# USBCONN_USBC16.net
KiCad netlist of a schematic drawn in Altium Designer
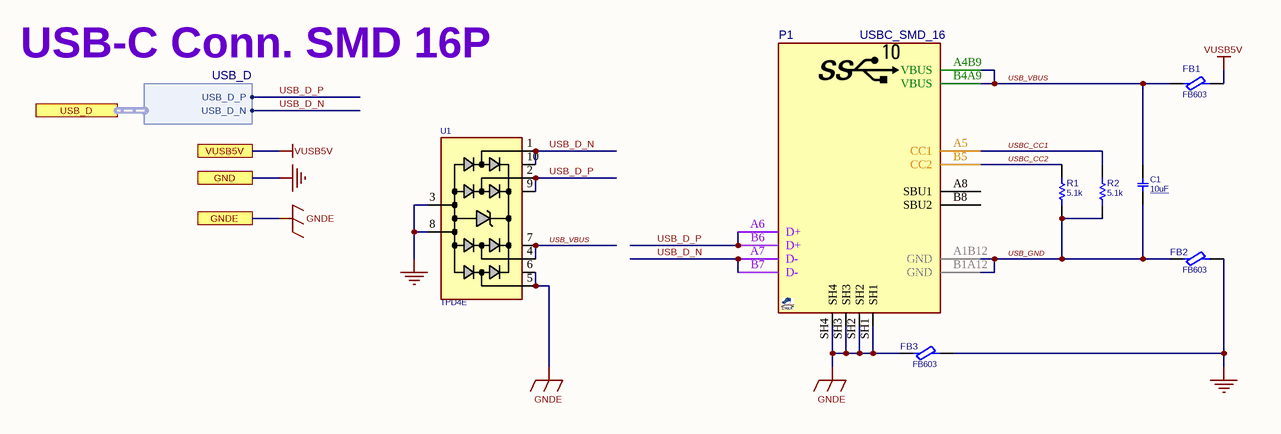
[diagram p0: USBCONN_USBC16.SchDoc]

(export (version "E")
  (design (tool "Eeschema 10.0.6"))
  (components
    (comp (ref "C1")
      (value "10uF")
      (footprint "C0402")
      (description "CAP, MLCC")
      (fields (field (name "MANF") "Murata"))
      (libsource (lib "mlcc_smd_passive") (part "CAP_SMD_MLCC"))
    )
    (comp (ref "FB1")
      (value "FB603")
      (footprint "L0603")
      (description "FERRITE_Bead, 0603, 1.3A, 150mOhm, 600@100MHz")
      (fields (field (name "MANF") "MURATA") (field (name "MANF_P#") "BLM18KG601SN1D"))
      (libsource (lib "emi_filter") (part "FBEAD_SMD_BLM18KG601"))
    )
    (comp (ref "FB2")
      (value "FB603")
      (footprint "L0603")
      (description "FERRITE_Bead, 0603, 1.3A, 150mOhm, 600@100MHz")
      (fields (field (name "MANF") "MURATA") (field (name "MANF_P#") "BLM18KG601SN1D"))
      (libsource (lib "emi_filter") (part "FBEAD_SMD_BLM18KG601"))
    )
    (comp (ref "FB3")
      (value "FB603")
      (footprint "L0603")
      (description "FERRITE_Bead, 0603, 1.3A, 150mOhm, 600@100MHz")
      (fields (field (name "MANF") "MURATA") (field (name "MANF_P#") "BLM18KG601SN1D"))
      (libsource (lib "emi_filter") (part "FBEAD_SMD_BLM18KG601"))
    )
    (comp (ref "P1")
      (value "USBC_SMD_16")
      (footprint "USBC_SMD_16_2171790001")
      (description "CONN, USB, Type C, USB 2.0, Right-Angle, SMD")
      (fields (field (name "MANF") "MOLEX") (field (name "MANF_P#") "2171790001"))
      (libsource (lib "USBC") (part "CONN_USBC_SMD_16_2171790001"))
    )
    (comp (ref "R1")
      (value "5.1k")
      (footprint "R0402")
      (description "RESISTOR, SMD")
      (libsource (lib "res_smd_passive") (part "RES_SMD"))
    )
    (comp (ref "R2")
      (value "5.1k")
      (footprint "R0402")
      (description "RESISTOR, SMD")
      (libsource (lib "res_smd_passive") (part "RES_SMD"))
    )
    (comp (ref "U1")
      (value "TPD4E")
      (footprint "SON50_10_2510E")
      (description "TVS, ESD PROTECT, 4CH,")
      (fields (field (name "MANF_P#") "TPD4E05U06DQA") (field (name "MANF") "Texas Instruments"))
      (libsource (lib "protect_tvs_esd_fuse") (part "TVS_X4_TPD4E05U06"))
    )
  )
  (nets
    (net (code "2") (name "/USBC_CC1") (class "Default")
      (node (ref "P1") (pin "A5") (pinfunction "CC1_A5") (pintype "passive"))
      (node (ref "R2") (pin "2") (pinfunction "2_2") (pintype "passive"))
    )
    (net (code "3") (name "/USBC_CC2") (class "Default")
      (node (ref "P1") (pin "B5") (pinfunction "CC2_B5") (pintype "passive"))
      (node (ref "R1") (pin "2") (pinfunction "2_2") (pintype "passive"))
    )
    (net (code "4") (name "/USB_D_N") (class "Default")
      (node (ref "P1") (pin "A7") (pinfunction "D-_A7") (pintype "passive"))
      (node (ref "P1") (pin "B7") (pinfunction "D-_B7") (pintype "passive"))
      (node (ref "U1") (pin "1") (pinfunction "1_1") (pintype "passive"))
      (node (ref "U1") (pin "10") (pinfunction "10_10") (pintype "passive"))
    )
    (net (code "5") (name "/USB_D_P") (class "Default")
      (node (ref "P1") (pin "A6") (pinfunction "D+_A6") (pintype "passive"))
      (node (ref "P1") (pin "B6") (pinfunction "D+_B6") (pintype "passive"))
      (node (ref "U1") (pin "2") (pinfunction "2_2") (pintype "passive"))
      (node (ref "U1") (pin "9") (pinfunction "9_9") (pintype "passive"))
    )
    (net (code "6") (name "/USB_GND") (class "Default")
      (node (ref "C1") (pin "2") (pinfunction "2_2") (pintype "passive"))
      (node (ref "FB2") (pin "1") (pinfunction "1_1") (pintype "passive"))
      (node (ref "P1") (pin "A1B12") (pinfunction "GND_A1B12") (pintype "passive"))
      (node (ref "P1") (pin "B1A12") (pinfunction "GND_B1A12") (pintype "passive"))
      (node (ref "R1") (pin "1") (pinfunction "1_1") (pintype "passive"))
      (node (ref "R2") (pin "1") (pinfunction "1_1") (pintype "passive"))
    )
    (net (code "7") (name "/USB_VBUS") (class "Default")
      (node (ref "C1") (pin "1") (pinfunction "1_1") (pintype "passive"))
      (node (ref "FB1") (pin "1") (pinfunction "1_1") (pintype "passive"))
      (node (ref "P1") (pin "A4B9") (pinfunction "VBUS_A4B9") (pintype "passive"))
      (node (ref "P1") (pin "B4A9") (pinfunction "VBUS_B4A9") (pintype "passive"))
      (node (ref "U1") (pin "4") (pinfunction "4_4") (pintype "passive"))
      (node (ref "U1") (pin "7") (pinfunction "7_7") (pintype "passive"))
    )
    (net (code "9") (name "GND") (class "Default")
      (node (ref "FB2") (pin "2") (pinfunction "2_2") (pintype "passive"))
      (node (ref "FB3") (pin "2") (pinfunction "2_2") (pintype "passive"))
      (node (ref "U1") (pin "3") (pinfunction "3_3") (pintype "passive"))
      (node (ref "U1") (pin "8") (pinfunction "8_8") (pintype "passive"))
    )
    (net (code "10") (name "GNDE") (class "Default")
      (node (ref "FB3") (pin "1") (pinfunction "1_1") (pintype "passive"))
      (node (ref "P1") (pin "SH1") (pinfunction "SH1_SH1") (pintype "passive"))
      (node (ref "P1") (pin "SH2") (pinfunction "SH2_SH2") (pintype "passive"))
      (node (ref "P1") (pin "SH3") (pinfunction "SH3_SH3") (pintype "passive"))
      (node (ref "P1") (pin "SH4") (pinfunction "SH4_SH4") (pintype "passive"))
      (node (ref "U1") (pin "5") (pinfunction "5_5") (pintype "passive"))
      (node (ref "U1") (pin "6") (pinfunction "6_6") (pintype "passive"))
    )
    (net (code "11") (name "VUSB5V") (class "Default")
      (node (ref "FB1") (pin "2") (pinfunction "2_2") (pintype "passive"))
    )
    (net (code "12") (name "unconnected-(P1-SBU1-PadA8)") (class "Default")
      (node (ref "P1") (pin "A8") (pinfunction "SBU1_A8") (pintype "passive"))
    )
    (net (code "13") (name "unconnected-(P1-SBU2-PadB8)") (class "Default")
      (node (ref "P1") (pin "B8") (pinfunction "SBU2_B8") (pintype "passive"))
    )
  )
)
